# Spinn5Power.net
KiCad netlist of a schematic drawn in Altium Designer
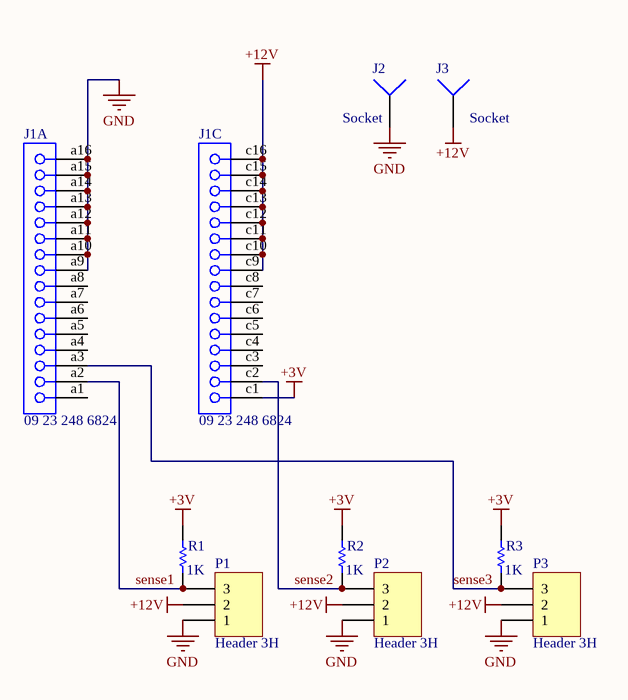
[diagram p0: Spinn5Power.SchDoc]

(export (version "E")
  (design (tool "Eeschema 10.0.6"))
  (components
    (comp (ref "J1")
      (value "09 23 248 6824")
      (footprint "0923248x824")
      (fields (field (name "PUBLISHER") "Altium Limited"))
      (libsource (lib "HARTING DIN 41612 Type 2C") (part "09 23 248 6824"))
    )
    (comp (ref "J2")
      (value "Socket")
      (footprint "PIN1")
      (fields (field (name "PUBLISHER") "Altium Limited"))
      (libsource (lib "Miscellaneous Connectors") (part "Socket"))
    )
    (comp (ref "J3")
      (value "Socket")
      (footprint "PIN1")
      (fields (field (name "PUBLISHER") "Altium Limited"))
      (libsource (lib "Miscellaneous Connectors") (part "Socket"))
    )
    (comp (ref "P1")
      (value "Header 3H")
      (footprint "HDR1X3H")
      (description "Header, 3-Pin, Right Angle")
      (fields (field (name "PUBLISHER") "Altium Limited"))
      (libsource (lib "Miscellaneous Connectors") (part "Header 3H"))
    )
    (comp (ref "P2")
      (value "Header 3H")
      (footprint "HDR1X3H")
      (description "Header, 3-Pin, Right Angle")
      (fields (field (name "PUBLISHER") "Altium Limited"))
      (libsource (lib "Miscellaneous Connectors") (part "Header 3H"))
    )
    (comp (ref "P3")
      (value "Header 3H")
      (footprint "HDR1X3H")
      (description "Header, 3-Pin, Right Angle")
      (fields (field (name "PUBLISHER") "Altium Limited"))
      (libsource (lib "Miscellaneous Connectors") (part "Header 3H"))
    )
    (comp (ref "R1")
      (value "1K")
      (footprint "AXIAL-0.3")
      (description "Resistor")
      (fields (field (name "Comment") "Res1") (field (name "PUBLISHER") "Altium Limited"))
      (libsource (lib "Miscellaneous Devices") (part "Res1"))
    )
    (comp (ref "R2")
      (value "1K")
      (footprint "AXIAL-0.3")
      (description "Resistor")
      (fields (field (name "Comment") "Res1") (field (name "PUBLISHER") "Altium Limited"))
      (libsource (lib "Miscellaneous Devices") (part "Res1"))
    )
    (comp (ref "R3")
      (value "1K")
      (footprint "AXIAL-0.3")
      (description "Resistor")
      (fields (field (name "Comment") "Res1") (field (name "PUBLISHER") "Altium Limited"))
      (libsource (lib "Miscellaneous Devices") (part "Res1"))
    )
  )
  (nets
    (net (code "1") (name "+3V") (class "Default")
      (node (ref "J1") (pin "c1") (pinfunction "c1_c1") (pintype "passive"))
      (node (ref "R1") (pin "2") (pinfunction "2_2") (pintype "passive"))
      (node (ref "R2") (pin "2") (pinfunction "2_2") (pintype "passive"))
      (node (ref "R3") (pin "2") (pinfunction "2_2") (pintype "passive"))
    )
    (net (code "2") (name "+12V") (class "Default")
      (node (ref "J1") (pin "c10") (pinfunction "c10_c10") (pintype "passive"))
      (node (ref "J1") (pin "c11") (pinfunction "c11_c11") (pintype "passive"))
      (node (ref "J1") (pin "c12") (pinfunction "c12_c12") (pintype "passive"))
      (node (ref "J1") (pin "c13") (pinfunction "c13_c13") (pintype "passive"))
      (node (ref "J1") (pin "c14") (pinfunction "c14_c14") (pintype "passive"))
      (node (ref "J1") (pin "c15") (pinfunction "c15_c15") (pintype "passive"))
      (node (ref "J1") (pin "c16") (pinfunction "c16_c16") (pintype "passive"))
      (node (ref "J1") (pin "c9") (pinfunction "c9_c9") (pintype "passive"))
      (node (ref "J3") (pin "1") (pinfunction "1_1") (pintype "passive"))
      (node (ref "P1") (pin "2") (pinfunction "2_2") (pintype "passive"))
      (node (ref "P2") (pin "2") (pinfunction "2_2") (pintype "passive"))
      (node (ref "P3") (pin "2") (pinfunction "2_2") (pintype "passive"))
    )
    (net (code "3") (name "/sense1") (class "Default")
      (node (ref "J1") (pin "a2") (pinfunction "a2_a2") (pintype "passive"))
      (node (ref "P1") (pin "3") (pinfunction "3_3") (pintype "passive"))
      (node (ref "R1") (pin "1") (pinfunction "1_1") (pintype "passive"))
    )
    (net (code "4") (name "/sense2") (class "Default")
      (node (ref "J1") (pin "c2") (pinfunction "c2_c2") (pintype "passive"))
      (node (ref "P2") (pin "3") (pinfunction "3_3") (pintype "passive"))
      (node (ref "R2") (pin "1") (pinfunction "1_1") (pintype "passive"))
    )
    (net (code "5") (name "/sense3") (class "Default")
      (node (ref "J1") (pin "a3") (pinfunction "a3_a3") (pintype "passive"))
      (node (ref "P3") (pin "3") (pinfunction "3_3") (pintype "passive"))
      (node (ref "R3") (pin "1") (pinfunction "1_1") (pintype "passive"))
    )
    (net (code "6") (name "GND") (class "Default")
      (node (ref "J1") (pin "a10") (pinfunction "a10_a10") (pintype "passive"))
      (node (ref "J1") (pin "a11") (pinfunction "a11_a11") (pintype "passive"))
      (node (ref "J1") (pin "a12") (pinfunction "a12_a12") (pintype "passive"))
      (node (ref "J1") (pin "a13") (pinfunction "a13_a13") (pintype "passive"))
      (node (ref "J1") (pin "a14") (pinfunction "a14_a14") (pintype "passive"))
      (node (ref "J1") (pin "a15") (pinfunction "a15_a15") (pintype "passive"))
      (node (ref "J1") (pin "a16") (pinfunction "a16_a16") (pintype "passive"))
      (node (ref "J1") (pin "a9") (pinfunction "a9_a9") (pintype "passive"))
      (node (ref "J2") (pin "1") (pinfunction "1_1") (pintype "passive"))
      (node (ref "P1") (pin "1") (pinfunction "1_1") (pintype "passive"))
      (node (ref "P2") (pin "1") (pinfunction "1_1") (pintype "passive"))
      (node (ref "P3") (pin "1") (pinfunction "1_1") (pintype "passive"))
    )
    (net (code "7") (name "unconnected-(J1-Pada1)") (class "Default")
      (node (ref "J1") (pin "a1") (pinfunction "a1_a1") (pintype "passive"))
    )
    (net (code "8") (name "unconnected-(J1-Pada4)") (class "Default")
      (node (ref "J1") (pin "a4") (pinfunction "a4_a4") (pintype "passive"))
    )
    (net (code "9") (name "unconnected-(J1-Pada5)") (class "Default")
      (node (ref "J1") (pin "a5") (pinfunction "a5_a5") (pintype "passive"))
    )
    (net (code "10") (name "unconnected-(J1-Pada6)") (class "Default")
      (node (ref "J1") (pin "a6") (pinfunction "a6_a6") (pintype "passive"))
    )
    (net (code "11") (name "unconnected-(J1-Pada7)") (class "Default")
      (node (ref "J1") (pin "a7") (pinfunction "a7_a7") (pintype "passive"))
    )
    (net (code "12") (name "unconnected-(J1-Pada8)") (class "Default")
      (node (ref "J1") (pin "a8") (pinfunction "a8_a8") (pintype "passive"))
    )
    (net (code "13") (name "unconnected-(J1-Padc3)") (class "Default")
      (node (ref "J1") (pin "c3") (pinfunction "c3_c3") (pintype "passive"))
    )
    (net (code "14") (name "unconnected-(J1-Padc4)") (class "Default")
      (node (ref "J1") (pin "c4") (pinfunction "c4_c4") (pintype "passive"))
    )
    (net (code "15") (name "unconnected-(J1-Padc5)") (class "Default")
      (node (ref "J1") (pin "c5") (pinfunction "c5_c5") (pintype "passive"))
    )
    (net (code "16") (name "unconnected-(J1-Padc6)") (class "Default")
      (node (ref "J1") (pin "c6") (pinfunction "c6_c6") (pintype "passive"))
    )
    (net (code "17") (name "unconnected-(J1-Padc7)") (class "Default")
      (node (ref "J1") (pin "c7") (pinfunction "c7_c7") (pintype "passive"))
    )
    (net (code "18") (name "unconnected-(J1-Padc8)") (class "Default")
      (node (ref "J1") (pin "c8") (pinfunction "c8_c8") (pintype "passive"))
    )
  )
)
